# SCH.net
KiCad netlist of a schematic drawn in EasyEDA Pro
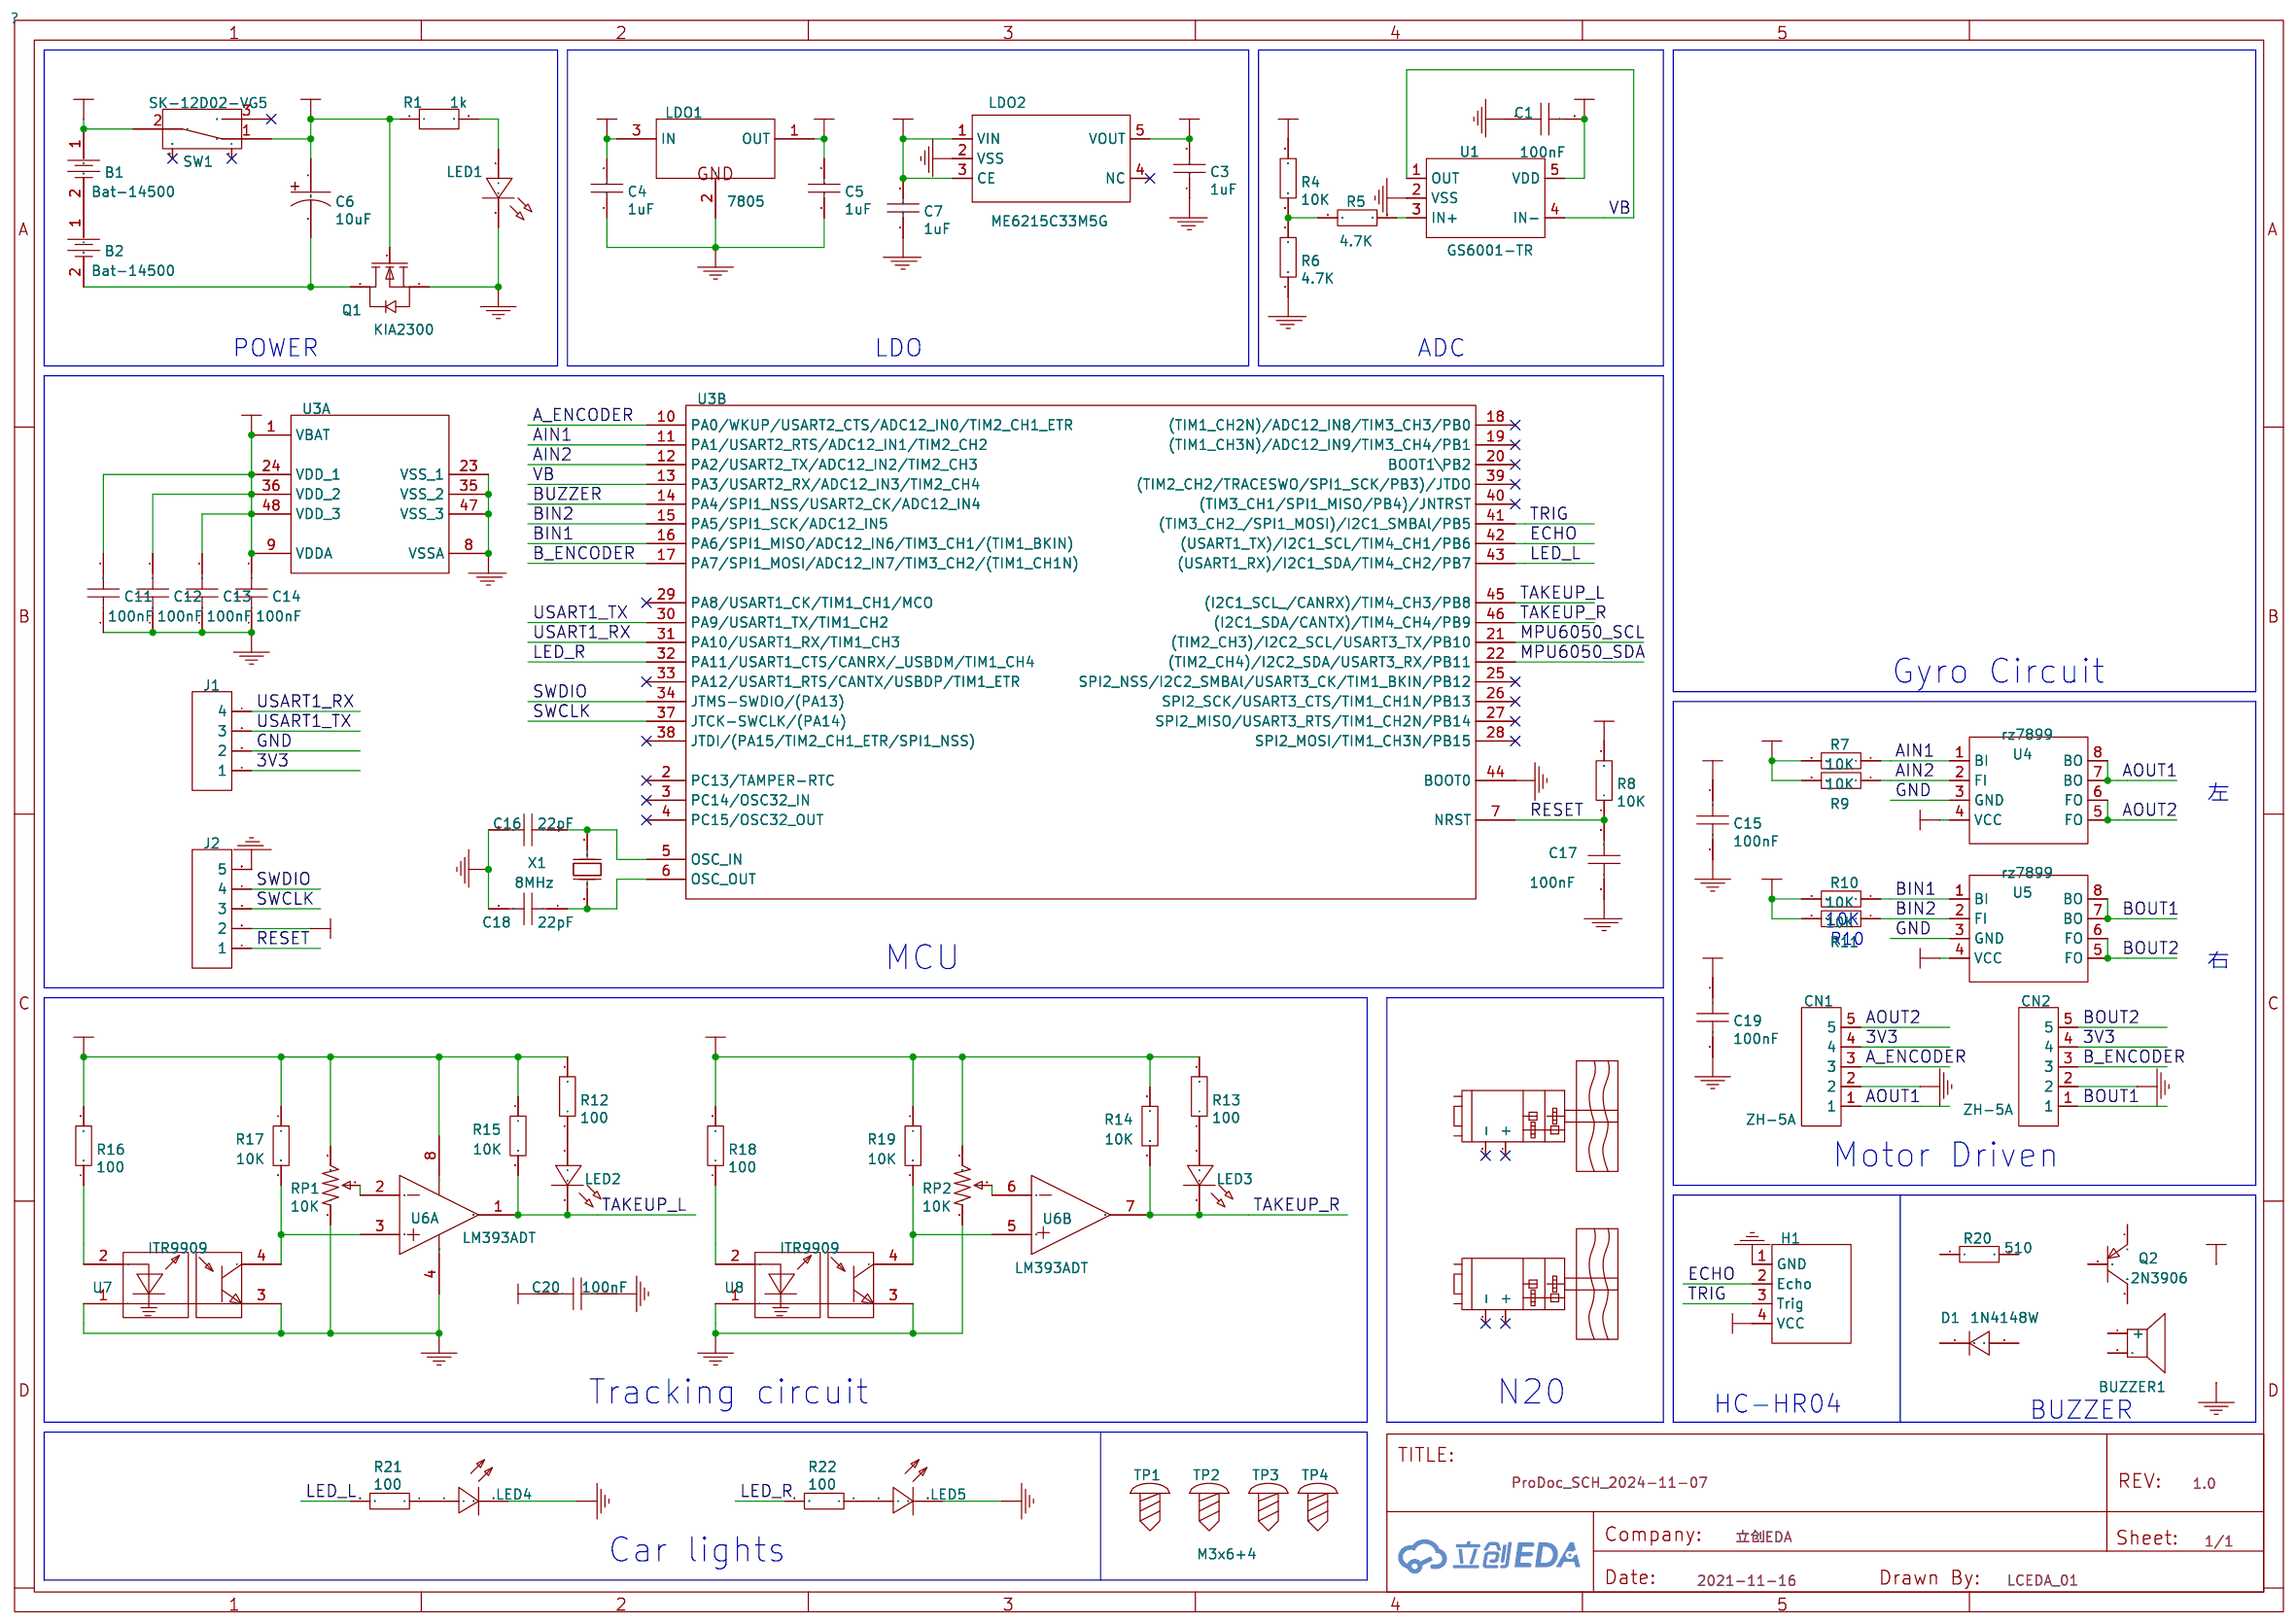
[diagram p0: schematic sheet]

(export (version "E")
  (design (tool "Eeschema 10.0.6"))
  (components
    (comp (ref "ASS_1")
      (value "直流电机N20")
      (footprint "easyedapro:直流电机N20_水平装配")
      (libsource (lib "easyedapro") (part "直流电机N20"))
    )
    (comp (ref "ASS_2")
      (value "直流电机N20")
      (footprint "easyedapro:直流电机N20_水平装配")
      (libsource (lib "easyedapro") (part "直流电机N20"))
    )
    (comp (ref "B1")
      (value "Bat-14500")
      (footprint "easyedapro:BAT-5AA_JX")
      (libsource (lib "easyedapro") (part "Bat-14500"))
    )
    (comp (ref "B2")
      (value "Bat-14500")
      (footprint "easyedapro:BAT-5AA_JX")
      (libsource (lib "easyedapro") (part "Bat-14500"))
    )
    (comp (ref "BUZZER1")
      (value "TMB12A12")
      (footprint "easyedapro:BUZ-TH_BD12.0-P7.60-D0.6-FD")
      (fields (field (name "Manufacturer") "HNDZ"))
      (libsource (lib "easyedapro") (part "TMB12A12"))
    )
    (comp (ref "C1")
      (value "100nF")
      (footprint "easyedapro:C0603")
      (fields (field (name "Manufacturer Part") "CC0603KRX7R9BB104") (field (name "Manufacturer") "YAGEO"))
      (libsource (lib "easyedapro") (part "100nF"))
    )
    (comp (ref "C3")
      (value "1uF")
      (footprint "easyedapro:C0603")
      (fields (field (name "Manufacturer Part") "CC0603KRX5R8BB105") (field (name "Manufacturer") "YAGEO"))
      (libsource (lib "easyedapro") (part "1uF"))
    )
    (comp (ref "C4")
      (value "1uF")
      (footprint "easyedapro:C0603")
      (fields (field (name "Manufacturer Part") "CC0603KRX5R8BB105") (field (name "Manufacturer") "YAGEO"))
      (libsource (lib "easyedapro") (part "1uF"))
    )
    (comp (ref "C5")
      (value "1uF")
      (footprint "easyedapro:C0603")
      (fields (field (name "Manufacturer Part") "CC0603KRX5R8BB105") (field (name "Manufacturer") "YAGEO"))
      (libsource (lib "easyedapro") (part "1uF"))
    )
    (comp (ref "C6")
      (value "10uF")
      (footprint "easyedapro:CAP-SMD_L3.2-W1.6")
      (fields (field (name "Manufacturer Part") "CA45-A-16V-10μF-K") (field (name "Manufacturer") "TORCH"))
      (libsource (lib "easyedapro") (part "10uF"))
    )
    (comp (ref "C7")
      (value "1uF")
      (footprint "easyedapro:C0603")
      (fields (field (name "Manufacturer Part") "CC0603KRX5R8BB105") (field (name "Manufacturer") "YAGEO"))
      (libsource (lib "easyedapro") (part "1uF"))
    )
    (comp (ref "C11")
      (value "100nF")
      (footprint "easyedapro:C0603")
      (fields (field (name "Manufacturer Part") "CC0603KRX7R9BB104") (field (name "Manufacturer") "YAGEO"))
      (libsource (lib "easyedapro") (part "100nF"))
    )
    (comp (ref "C12")
      (value "100nF")
      (footprint "easyedapro:C0603")
      (fields (field (name "Manufacturer Part") "CC0603KRX7R9BB104") (field (name "Manufacturer") "YAGEO"))
      (libsource (lib "easyedapro") (part "100nF"))
    )
    (comp (ref "C13")
      (value "100nF")
      (footprint "easyedapro:C0603")
      (fields (field (name "Manufacturer Part") "CC0603KRX7R9BB104") (field (name "Manufacturer") "YAGEO"))
      (libsource (lib "easyedapro") (part "100nF"))
    )
    (comp (ref "C14")
      (value "100nF")
      (footprint "easyedapro:C0603")
      (fields (field (name "Manufacturer Part") "CC0603KRX7R9BB104") (field (name "Manufacturer") "YAGEO"))
      (libsource (lib "easyedapro") (part "100nF"))
    )
    (comp (ref "C15")
      (value "100nF")
      (footprint "easyedapro:C0603")
      (fields (field (name "Manufacturer Part") "CC0603KRX7R9BB104") (field (name "Manufacturer") "YAGEO"))
      (libsource (lib "easyedapro") (part "100nF"))
    )
    (comp (ref "C16")
      (value "22pF")
      (footprint "easyedapro:C0603")
      (fields (field (name "Manufacturer Part") "CC0603FRNPO9BN220") (field (name "Manufacturer") "YAGEO"))
      (libsource (lib "easyedapro") (part "22pF"))
    )
    (comp (ref "C17")
      (value "100nF")
      (footprint "easyedapro:C0603")
      (fields (field (name "Manufacturer Part") "CC0603KRX7R9BB104") (field (name "Manufacturer") "YAGEO"))
      (libsource (lib "easyedapro") (part "100nF"))
    )
    (comp (ref "C18")
      (value "22pF")
      (footprint "easyedapro:C0603")
      (fields (field (name "Manufacturer Part") "CC0603FRNPO9BN220") (field (name "Manufacturer") "YAGEO"))
      (libsource (lib "easyedapro") (part "22pF"))
    )
    (comp (ref "C19")
      (value "100nF")
      (footprint "easyedapro:C0603")
      (fields (field (name "Manufacturer Part") "CC0603KRX7R9BB104") (field (name "Manufacturer") "YAGEO"))
      (libsource (lib "easyedapro") (part "100nF"))
    )
    (comp (ref "C20")
      (value "100nF")
      (footprint "easyedapro:C0603")
      (fields (field (name "Manufacturer Part") "CC0603KRX7R9BB104") (field (name "Manufacturer") "YAGEO"))
      (libsource (lib "easyedapro") (part "100nF"))
    )
    (comp (ref "CN1")
      (value "ZH-5A")
      (footprint "easyedapro:CONN-TH_5P-P1.50_ZH-5A")
      (fields (field (name "Manufacturer") "BOOMELE"))
      (libsource (lib "easyedapro") (part "ZH-5A"))
    )
    (comp (ref "CN2")
      (value "ZH-5A")
      (footprint "easyedapro:CONN-TH_5P-P1.50_ZH-5A")
      (fields (field (name "Manufacturer") "BOOMELE"))
      (libsource (lib "easyedapro") (part "ZH-5A"))
    )
    (comp (ref "D1")
      (value "1N4148W")
      (footprint "easyedapro:SOD-123FL_L2.6-W1.6-LS3.4-RD")
      (fields (field (name "Manufacturer") "Tak Cheong"))
      (libsource (lib "easyedapro") (part "1N4148W"))
    )
    (comp (ref "H1")
      (value "超声波测距模块_HC-HR04")
      (footprint "easyedapro:HC-HR04")
      (libsource (lib "easyedapro") (part "超声波测距模块_HC-HR04"))
    )
    (comp (ref "J1")
      (value "HDR-M-2.54_1x4")
      (footprint "easyedapro:HDR-M-2.54_1X4")
      (libsource (lib "easyedapro") (part "HDR-M-2.54_1x4"))
    )
    (comp (ref "J2")
      (value "HDR-M-2.54_1x5")
      (footprint "easyedapro:HDR-M-2.54_1X5")
      (libsource (lib "easyedapro") (part "HDR-M-2.54_1x5"))
    )
    (comp (ref "LDO1")
      (value "7805")
      (footprint "easyedapro:SOT-89-3_L4.5-W2.5-P1.50-LS4.2-BR")
      (fields (field (name "Manufacturer Part") "CJ78L05") (field (name "Manufacturer") "CJ"))
      (libsource (lib "easyedapro") (part "7805"))
    )
    (comp (ref "LDO2")
      (value "ME6215C33M5G")
      (footprint "easyedapro:SOT-23-5_L3.0-W1.7-P0.95-LS2.8-BR")
      (fields (field (name "Manufacturer") "MICRONE"))
      (libsource (lib "easyedapro") (part "ME6215C33M5G"))
    )
    (comp (ref "LED1")
      (value "LED-0603_R")
      (footprint "easyedapro:LED0603_RED")
      (fields
        (field (name "Manufacturer Part") "19-217/R6C-AL1M2VY/3T")
        (field (name "Manufacturer") "EVERLIGHT(台湾亿光)")
      )
      (libsource (lib "easyedapro") (part "LED-0603_R"))
    )
    (comp (ref "LED2")
      (value "LED-0805_G")
      (footprint "easyedapro:LED0603_GREEN")
      (fields (field (name "Manufacturer Part") "NCD0805G1") (field (name "Manufacturer") "国星光电"))
      (libsource (lib "easyedapro") (part "LED-0805_G"))
    )
    (comp (ref "LED3")
      (value "LED-0805_G")
      (footprint "easyedapro:LED0603_GREEN")
      (fields (field (name "Manufacturer Part") "NCD0805G1") (field (name "Manufacturer") "国星光电"))
      (libsource (lib "easyedapro") (part "LED-0805_G"))
    )
    (comp (ref "LED4")
      (value "TJ-L5FCMYGTDLSFLC6TW-A5")
      (footprint "easyedapro:LED-TH-5MM_P2.54-L")
      (fields (field (name "Manufacturer") "TOGIALED"))
      (libsource (lib "easyedapro") (part "TJ-L5FCMYGTDLSFLC6TW-A5"))
    )
    (comp (ref "LED5")
      (value "TJ-L5FCMYGTDLSFLC6TW-A5")
      (footprint "easyedapro:LED-TH-5MM_P2.54-L")
      (fields (field (name "Manufacturer") "TOGIALED"))
      (libsource (lib "easyedapro") (part "TJ-L5FCMYGTDLSFLC6TW-A5"))
    )
    (comp (ref "Q1")
      (value "KIA2300")
      (footprint "easyedapro:SOT-23_L2.9-W1.3-P1.90-LS2.4-BR")
      (fields (field (name "Manufacturer") "KIA"))
      (libsource (lib "easyedapro") (part "KIA2300"))
    )
    (comp (ref "Q2")
      (value "2N3906")
      (footprint "easyedapro:SOT-23-3_L2.9-W1.6-P1.90-LS2.8-TR-CW")
      (fields (field (name "Manufacturer Part") "2N3906S-RTK/PS") (field (name "Manufacturer") "KEC"))
      (libsource (lib "easyedapro") (part "2N3906"))
    )
    (comp (ref "R1") (value "1k") (footprint "easyedapro:R0603") (libsource (lib "easyedapro") (part "1k")))
    (comp (ref "R4")
      (value "10K")
      (footprint "easyedapro:R0603")
      (fields (field (name "Manufacturer Part") "AR03BTCX1002") (field (name "Manufacturer") "Viking Tech"))
      (libsource (lib "easyedapro") (part "10K"))
    )
    (comp (ref "R5")
      (value "4.7K")
      (footprint "easyedapro:R0603")
      (fields (field (name "Manufacturer Part") "RS-03K4701FT") (field (name "Manufacturer") "FH"))
      (libsource (lib "easyedapro") (part "4.7K"))
    )
    (comp (ref "R6")
      (value "4.7K")
      (footprint "easyedapro:R0603")
      (fields (field (name "Manufacturer Part") "RS-03K4701FT") (field (name "Manufacturer") "FH"))
      (libsource (lib "easyedapro") (part "4.7K"))
    )
    (comp (ref "R7")
      (value "10K")
      (footprint "easyedapro:R0603")
      (fields (field (name "Manufacturer Part") "AR03BTCX1002") (field (name "Manufacturer") "Viking Tech"))
      (libsource (lib "easyedapro") (part "10K"))
    )
    (comp (ref "R8")
      (value "10K")
      (footprint "easyedapro:R0603")
      (fields (field (name "Manufacturer Part") "AR03BTCX1002") (field (name "Manufacturer") "Viking Tech"))
      (libsource (lib "easyedapro") (part "10K"))
    )
    (comp (ref "R9")
      (value "10K")
      (footprint "easyedapro:R0603")
      (fields (field (name "Manufacturer Part") "AR03BTCX1002") (field (name "Manufacturer") "Viking Tech"))
      (libsource (lib "easyedapro") (part "10K"))
    )
    (comp (ref "R10")
      (value "10K")
      (footprint "easyedapro:R0603")
      (fields (field (name "Manufacturer Part") "AR03BTCX1002") (field (name "Manufacturer") "Viking Tech"))
      (libsource (lib "easyedapro") (part "10K"))
    )
    (comp (ref "R11")
      (value "10K")
      (footprint "easyedapro:R0603")
      (fields (field (name "Manufacturer Part") "AR03BTCX1002") (field (name "Manufacturer") "Viking Tech"))
      (libsource (lib "easyedapro") (part "10K"))
    )
    (comp (ref "R12")
      (value "100")
      (footprint "easyedapro:R0603")
      (fields (field (name "Manufacturer Part") "RS-03K101JT") (field (name "Manufacturer") "FH"))
      (libsource (lib "easyedapro") (part "100"))
    )
    (comp (ref "R13")
      (value "100")
      (footprint "easyedapro:R0603")
      (fields (field (name "Manufacturer Part") "RS-03K101JT") (field (name "Manufacturer") "FH"))
      (libsource (lib "easyedapro") (part "100"))
    )
    (comp (ref "R14")
      (value "10K")
      (footprint "easyedapro:R0603")
      (fields (field (name "Manufacturer Part") "AR03BTCX1002") (field (name "Manufacturer") "Viking Tech"))
      (libsource (lib "easyedapro") (part "10K"))
    )
    (comp (ref "R15")
      (value "10K")
      (footprint "easyedapro:R0603")
      (fields (field (name "Manufacturer Part") "AR03BTCX1002") (field (name "Manufacturer") "Viking Tech"))
      (libsource (lib "easyedapro") (part "10K"))
    )
    (comp (ref "R16")
      (value "100")
      (footprint "easyedapro:R0603")
      (fields (field (name "Manufacturer Part") "RS-03K101JT") (field (name "Manufacturer") "FH"))
      (libsource (lib "easyedapro") (part "100"))
    )
    (comp (ref "R17")
      (value "10K")
      (footprint "easyedapro:R0603")
      (fields (field (name "Manufacturer Part") "AR03BTCX1002") (field (name "Manufacturer") "Viking Tech"))
      (libsource (lib "easyedapro") (part "10K"))
    )
    (comp (ref "R18")
      (value "100")
      (footprint "easyedapro:R0603")
      (fields (field (name "Manufacturer Part") "RS-03K101JT") (field (name "Manufacturer") "FH"))
      (libsource (lib "easyedapro") (part "100"))
    )
    (comp (ref "R19")
      (value "10K")
      (footprint "easyedapro:R0603")
      (fields (field (name "Manufacturer Part") "AR03BTCX1002") (field (name "Manufacturer") "Viking Tech"))
      (libsource (lib "easyedapro") (part "10K"))
    )
    (comp (ref "R20")
      (value "510")
      (footprint "easyedapro:R0603")
      (fields (field (name "Manufacturer Part") "ERJUP3J511V") (field (name "Manufacturer") "PANASONIC"))
      (libsource (lib "easyedapro") (part "510"))
    )
    (comp (ref "R21")
      (value "100")
      (footprint "easyedapro:R0603")
      (fields (field (name "Manufacturer Part") "RS-03K101JT") (field (name "Manufacturer") "FH"))
      (libsource (lib "easyedapro") (part "100"))
    )
    (comp (ref "R22")
      (value "100")
      (footprint "easyedapro:R0603")
      (fields (field (name "Manufacturer Part") "RS-03K101JT") (field (name "Manufacturer") "FH"))
      (libsource (lib "easyedapro") (part "100"))
    )
    (comp (ref "RP1") (value "10K") (footprint "easyedapro:10K贴片可调电阻") (libsource (lib "") (part "10K_1")))
    (comp (ref "RP2") (value "10K") (footprint "easyedapro:10K贴片可调电阻") (libsource (lib "") (part "10K_1")))
    (comp (ref "SW1")
      (value "SK-12D02-VG5")
      (footprint "easyedapro:SW-TH_SK-12D02VG3")
      (fields (field (name "Manufacturer") "Rectangular Connectors - Contacts"))
      (libsource (lib "easyedapro") (part "SK-12D02-VG5"))
    )
    (comp (ref "TP1")
      (value "M3x6+4")
      (footprint "easyedapro:M3铜柱")
      (libsource (lib "easyedapro") (part "M3x6+4"))
    )
    (comp (ref "TP2")
      (value "M3x6+4")
      (footprint "easyedapro:M3铜柱")
      (libsource (lib "easyedapro") (part "M3x6+4"))
    )
    (comp (ref "TP3")
      (value "M3x6+4")
      (footprint "easyedapro:M3铜柱")
      (libsource (lib "easyedapro") (part "M3x6+4"))
    )
    (comp (ref "TP4")
      (value "M3x6+4")
      (footprint "easyedapro:M3铜柱")
      (libsource (lib "easyedapro") (part "M3x6+4"))
    )
    (comp (ref "U1")
      (value "GS6001-TR")
      (footprint "easyedapro:SOT-23-5_L3.0-W1.7-P0.95-LS2.8-BR")
      (fields (field (name "Manufacturer") "Gainsil"))
      (libsource (lib "easyedapro") (part "GS6001-TR"))
    )
    (comp (ref "U3")
      (value "STM32F103C8T6")
      (footprint "easyedapro:LQFP-48_L7.0-W7.0-P0.50-LS9.0-BL")
      (libsource (lib "easyedapro") (part "STM32F103C8T6"))
    )
    (comp (ref "U4")
      (value "rz7899")
      (footprint "easyedapro:SOP-8_L4.9-W3.9-P1.27-LS6.0-BL")
      (fields (field (name "Manufacturer") "RZ"))
      (libsource (lib "easyedapro") (part "rz7899"))
    )
    (comp (ref "U5")
      (value "rz7899")
      (footprint "easyedapro:SOP-8_L4.9-W3.9-P1.27-LS6.0-BL")
      (fields (field (name "Manufacturer") "RZ"))
      (libsource (lib "easyedapro") (part "rz7899"))
    )
    (comp (ref "U6")
      (value "LM393ADT")
      (footprint "easyedapro:SOIC-8_L4.9-W3.9-P1.27-LS6.0-BL")
      (fields (field (name "Manufacturer") "STMicroelectronics"))
      (libsource (lib "easyedapro") (part "LM393ADT"))
    )
    (comp (ref "U7")
      (value "ITR9909")
      (footprint "easyedapro:OPTO-TH_ITR9909")
      (fields (field (name "Manufacturer") "EVERLIGHT"))
      (libsource (lib "easyedapro") (part "ITR9909"))
    )
    (comp (ref "U8")
      (value "ITR9909")
      (footprint "easyedapro:OPTO-TH_ITR9909")
      (fields (field (name "Manufacturer") "EVERLIGHT"))
      (libsource (lib "easyedapro") (part "ITR9909"))
    )
    (comp (ref "X1")
      (value "8MHz")
      (footprint "easyedapro:OSC-SMD_L5.0-W3.2")
      (fields (field (name "Manufacturer Part") "X50328MSB2GI") (field (name "Manufacturer") "YXC"))
      (libsource (lib "easyedapro") (part "8MHz"))
    )
  )
  (nets
    (net (code "1") (name "+5V") (class "Default")
      (node (ref "C5") (pin "2") (pinfunction "2_2") (pintype "input"))
      (node (ref "C7") (pin "2") (pinfunction "2_2") (pintype "input"))
      (node (ref "H1") (pin "4") (pinfunction "VCC_4") (pintype "unspecified"))
      (node (ref "LDO1") (pin "1") (pinfunction "OUT_1") (pintype "unspecified"))
      (node (ref "LDO2") (pin "1") (pinfunction "VIN_1") (pintype "unspecified"))
      (node (ref "LDO2") (pin "3") (pinfunction "CE_3") (pintype "unspecified"))
    )
    (net (code "2") (name "/AIN1") (class "Default")
      (node (ref "R7") (pin "1") (pinfunction "1_1") (pintype "unspecified"))
      (node (ref "U3") (pin "11") (pinfunction "PA1/USART2_RTS/ADC12_IN1/TIM2_CH2_11") (pintype "bidirectional"))
      (node (ref "U4") (pin "1") (pinfunction "BI_1") (pintype "unspecified"))
    )
    (net (code "3") (name "/AIN2") (class "Default")
      (node (ref "R9") (pin "1") (pinfunction "1_1") (pintype "unspecified"))
      (node (ref "U3") (pin "12") (pinfunction "PA2/USART2_TX/ADC12_IN2/TIM2_CH3_12") (pintype "bidirectional"))
      (node (ref "U4") (pin "2") (pinfunction "FI_2") (pintype "unspecified"))
    )
    (net (code "4") (name "/AOUT1") (class "Default")
      (node (ref "CN1") (pin "1") (pinfunction "1_1") (pintype "unspecified"))
      (node (ref "U4") (pin "7") (pinfunction "BO_7") (pintype "unspecified"))
      (node (ref "U4") (pin "8") (pinfunction "BO_8") (pintype "unspecified"))
    )
    (net (code "5") (name "/AOUT2") (class "Default")
      (node (ref "CN1") (pin "5") (pinfunction "5_5") (pintype "unspecified"))
      (node (ref "U4") (pin "5") (pinfunction "FO_5") (pintype "unspecified"))
      (node (ref "U4") (pin "6") (pinfunction "FO_6") (pintype "unspecified"))
    )
    (net (code "6") (name "/A_ENCODER") (class "Default")
      (node (ref "CN1") (pin "3") (pinfunction "3_3") (pintype "unspecified"))
      (node (ref "U3") (pin "10") (pinfunction "PA0/WKUP/USART2_CTS/ADC12_IN0/TIM2_CH1_ETR_10") (pintype "bidirectional"))
    )
    (net (code "7") (name "/BIN1") (class "Default")
      (node (ref "R10") (pin "1") (pinfunction "1_1") (pintype "unspecified"))
      (node (ref "U3") (pin "16") (pinfunction "PA6/SPI1_MISO/ADC12_IN6/TIM3_CH1/(TIM1_BKIN)_16") (pintype "bidirectional"))
      (node (ref "U5") (pin "1") (pinfunction "BI_1") (pintype "unspecified"))
    )
    (net (code "8") (name "/BIN2") (class "Default")
      (node (ref "R11") (pin "1") (pinfunction "1_1") (pintype "unspecified"))
      (node (ref "U3") (pin "15") (pinfunction "PA5/SPI1_SCK/ADC12_IN5_15") (pintype "bidirectional"))
      (node (ref "U5") (pin "2") (pinfunction "FI_2") (pintype "unspecified"))
    )
    (net (code "9") (name "/BOUT1") (class "Default")
      (node (ref "CN2") (pin "1") (pinfunction "1_1") (pintype "unspecified"))
      (node (ref "U5") (pin "7") (pinfunction "BO_7") (pintype "unspecified"))
      (node (ref "U5") (pin "8") (pinfunction "BO_8") (pintype "unspecified"))
    )
    (net (code "10") (name "/BOUT2") (class "Default")
      (node (ref "CN2") (pin "5") (pinfunction "5_5") (pintype "unspecified"))
      (node (ref "U5") (pin "5") (pinfunction "FO_5") (pintype "unspecified"))
      (node (ref "U5") (pin "6") (pinfunction "FO_6") (pintype "unspecified"))
    )
    (net (code "11") (name "/BUZZER") (class "Default")
      (node (ref "U3") (pin "14") (pinfunction "PA4/SPI1_NSS/USART2_CK/ADC12_IN4_14") (pintype "bidirectional"))
    )
    (net (code "12") (name "/B_ENCODER") (class "Default")
      (node (ref "CN2") (pin "3") (pinfunction "3_3") (pintype "unspecified"))
      (node (ref "U3") (pin "17") (pinfunction "PA7/SPI1_MOSI/ADC12_IN7/TIM3_CH2/(TIM1_CH1N)_17") (pintype "bidirectional"))
    )
    (net (code "13") (name "/ECHO") (class "Default")
      (node (ref "H1") (pin "2") (pinfunction "Echo_2") (pintype "unspecified"))
      (node (ref "U3") (pin "42") (pinfunction "(USART1_TX)/I2C1_SCL/TIM4_CH1/PB6_42") (pintype "bidirectional"))
    )
    (net (code "14") (name "/LED_L") (class "Default")
      (node (ref "R21") (pin "2") (pinfunction "2_2") (pintype "input"))
      (node (ref "U3") (pin "43") (pinfunction "(USART1_RX)/I2C1_SDA/TIM4_CH2/PB7_43") (pintype "bidirectional"))
    )
    (net (code "15") (name "/LED_R") (class "Default")
      (node (ref "R22") (pin "2") (pinfunction "2_2") (pintype "input"))
      (node (ref "U3") (pin "32") (pinfunction "PA11/USART1_CTS/CANRX/_USBDM/TIM1_CH4_32") (pintype "bidirectional"))
    )
    (net (code "16") (name "/MPU6050_SCL") (class "Default")
      (node (ref "U3") (pin "21") (pinfunction "(TIM2_CH3)/I2C2_SCL/USART3_TX/PB10_21") (pintype "bidirectional"))
    )
    (net (code "17") (name "/MPU6050_SDA") (class "Default")
      (node (ref "U3") (pin "22") (pinfunction "(TIM2_CH4)/I2C2_SDA/USART3_RX/PB11_22") (pintype "bidirectional"))
    )
    (net (code "18") (name "/RESET") (class "Default")
      (node (ref "C17") (pin "2") (pinfunction "2_2") (pintype "unspecified"))
      (node (ref "J2") (pin "1") (pinfunction "1_1") (pintype "unspecified"))
      (node (ref "R8") (pin "1") (pinfunction "1_1") (pintype "unspecified"))
      (node (ref "U3") (pin "7") (pinfunction "NRST_7") (pintype "bidirectional"))
    )
    (net (code "19") (name "/SWCLK") (class "Default")
      (node (ref "J2") (pin "3") (pinfunction "3_3") (pintype "unspecified"))
      (node (ref "U3") (pin "37") (pinfunction "JTCK-SWCLK/(PA14)_37") (pintype "bidirectional"))
    )
    (net (code "20") (name "/SWDIO") (class "Default")
      (node (ref "J2") (pin "4") (pinfunction "4_4") (pintype "unspecified"))
      (node (ref "U3") (pin "34") (pinfunction "JTMS-SWDIO/(PA13)_34") (pintype "bidirectional"))
    )
    (net (code "21") (name "/TAKEUP_L") (class "Default")
      (node (ref "LED2") (pin "2") (pinfunction "2_2") (pintype "unspecified"))
      (node (ref "R15") (pin "2") (pinfunction "2_2") (pintype "unspecified"))
      (node (ref "U3") (pin "45") (pinfunction "(I2C1_SCL_/CANRX)/TIM4_CH3/PB8_45") (pintype "bidirectional"))
      (node (ref "U6") (pin "1") (pinfunction "OUT_1") (pintype "output"))
    )
    (net (code "22") (name "/TAKEUP_R") (class "Default")
      (node (ref "LED3") (pin "2") (pinfunction "2_2") (pintype "unspecified"))
      (node (ref "R14") (pin "2") (pinfunction "2_2") (pintype "unspecified"))
      (node (ref "U3") (pin "46") (pinfunction "(I2C1_SDA/CANTX)/TIM4_CH4/PB9_46") (pintype "bidirectional"))
      (node (ref "U6") (pin "7") (pinfunction "OUT_7") (pintype "output"))
    )
    (net (code "23") (name "/TRIG") (class "Default")
      (node (ref "H1") (pin "3") (pinfunction "Trig_3") (pintype "unspecified"))
      (node (ref "U3") (pin "41") (pinfunction "(TIM3_CH2_/SPI1_MOSI)/I2C1_SMBAl/PB5_41") (pintype "bidirectional"))
    )
    (net (code "24") (name "/USART1_RX") (class "Default")
      (node (ref "J1") (pin "4") (pinfunction "4_4") (pintype "unspecified"))
      (node (ref "U3") (pin "31") (pinfunction "PA10/USART1_RX/TIM1_CH3_31") (pintype "bidirectional"))
    )
    (net (code "25") (name "/USART1_TX") (class "Default")
      (node (ref "J1") (pin "3") (pinfunction "3_3") (pintype "unspecified"))
      (node (ref "U3") (pin "30") (pinfunction "PA9/USART1_TX/TIM1_CH2_30") (pintype "bidirectional"))
    )
    (net (code "26") (name "/VB") (class "Default")
      (node (ref "U1") (pin "1") (pinfunction "OUT_1") (pintype "unspecified"))
      (node (ref "U1") (pin "4") (pinfunction "IN-_4") (pintype "unspecified"))
      (node (ref "U3") (pin "13") (pinfunction "PA3/USART2_RX/ADC12_IN3/TIM2_CH4_13") (pintype "bidirectional"))
    )
    (net (code "27") (name "3V3") (class "Default")
      (node (ref "C1") (pin "2") (pinfunction "2_2") (pintype "unspecified"))
      (node (ref "C11") (pin "2") (pinfunction "2_2") (pintype "unspecified"))
      (node (ref "C12") (pin "2") (pinfunction "2_2") (pintype "unspecified"))
      (node (ref "C13") (pin "2") (pinfunction "2_2") (pintype "unspecified"))
      (node (ref "C14") (pin "2") (pinfunction "2_2") (pintype "unspecified"))
      (node (ref "C20") (pin "1") (pinfunction "1_1") (pintype "unspecified"))
      (node (ref "C3") (pin "2") (pinfunction "2_2") (pintype "input"))
      (node (ref "CN1") (pin "4") (pinfunction "4_4") (pintype "unspecified"))
      (node (ref "CN2") (pin "4") (pinfunction "4_4") (pintype "unspecified"))
      (node (ref "J1") (pin "1") (pinfunction "1_1") (pintype "unspecified"))
      (node (ref "J2") (pin "2") (pinfunction "2_2") (pintype "unspecified"))
      (node (ref "LDO2") (pin "5") (pinfunction "VOUT_5") (pintype "unspecified"))
      (node (ref "R10") (pin "2") (pinfunction "2_2") (pintype "unspecified"))
      (node (ref "R11") (pin "2") (pinfunction "2_2") (pintype "unspecified"))
      (node (ref "R12") (pin "2") (pinfunction "2_2") (pintype "input"))
      (node (ref "R13") (pin "2") (pinfunction "2_2") (pintype "input"))
      (node (ref "R14") (pin "1") (pinfunction "1_1") (pintype "unspecified"))
      (node (ref "R15") (pin "1") (pinfunction "1_1") (pintype "unspecified"))
      (node (ref "R16") (pin "2") (pinfunction "2_2") (pintype "input"))
      (node (ref "R17") (pin "1") (pinfunction "1_1") (pintype "unspecified"))
      (node (ref "R18") (pin "2") (pinfunction "2_2") (pintype "input"))
      (node (ref "R19") (pin "1") (pinfunction "1_1") (pintype "unspecified"))
      (node (ref "R7") (pin "2") (pinfunction "2_2") (pintype "unspecified"))
      (node (ref "R8") (pin "2") (pinfunction "2_2") (pintype "unspecified"))
      (node (ref "R9") (pin "2") (pinfunction "2_2") (pintype "unspecified"))
      (node (ref "RP1") (pin "3") (pinfunction "3_3") (pintype "unspecified"))
      (node (ref "RP2") (pin "3") (pinfunction "3_3") (pintype "unspecified"))
      (node (ref "U1") (pin "5") (pinfunction "VDD_5") (pintype "unspecified"))
      (node (ref "U3") (pin "1") (pinfunction "VBAT_1") (pintype "unspecified"))
      (node (ref "U3") (pin "24") (pinfunction "VDD_1_24") (pintype "unspecified"))
      (node (ref "U3") (pin "36") (pinfunction "VDD_2_36") (pintype "unspecified"))
      (node (ref "U3") (pin "48") (pinfunction "VDD_3_48") (pintype "unspecified"))
      (node (ref "U3") (pin "9") (pinfunction "VDDA_9") (pintype "unspecified"))
      (node (ref "U6") (pin "8") (pinfunction "V+_8") (pintype "unspecified"))
    )
    (net (code "28") (name "GND") (class "Default")
      (node (ref "C1") (pin "1") (pinfunction "1_1") (pintype "unspecified"))
      (node (ref "C11") (pin "1") (pinfunction "1_1") (pintype "unspecified"))
      (node (ref "C12") (pin "1") (pinfunction "1_1") (pintype "unspecified"))
      (node (ref "C13") (pin "1") (pinfunction "1_1") (pintype "unspecified"))
      (node (ref "C14") (pin "1") (pinfunction "1_1") (pintype "unspecified"))
      (node (ref "C15") (pin "2") (pinfunction "2_2") (pintype "unspecified"))
      (node (ref "C16") (pin "2") (pinfunction "2_2") (pintype "unspecified"))
      (node (ref "C17") (pin "1") (pinfunction "1_1") (pintype "unspecified"))
      (node (ref "C18") (pin "2") (pinfunction "2_2") (pintype "unspecified"))
      (node (ref "C19") (pin "2") (pinfunction "2_2") (pintype "unspecified"))
      (node (ref "C20") (pin "2") (pinfunction "2_2") (pintype "unspecified"))
      (node (ref "C3") (pin "1") (pinfunction "1_1") (pintype "input"))
      (node (ref "C4") (pin "1") (pinfunction "1_1") (pintype "input"))
      (node (ref "C5") (pin "1") (pinfunction "1_1") (pintype "input"))
      (node (ref "C7") (pin "1") (pinfunction "1_1") (pintype "input"))
      (node (ref "CN1") (pin "2") (pinfunction "2_2") (pintype "unspecified"))
      (node (ref "CN2") (pin "2") (pinfunction "2_2") (pintype "unspecified"))
      (node (ref "H1") (pin "1") (pinfunction "GND_1") (pintype "unspecified"))
      (node (ref "J1") (pin "2") (pinfunction "2_2") (pintype "unspecified"))
      (node (ref "J2") (pin "5") (pinfunction "5_5") (pintype "unspecified"))
      (node (ref "LDO1") (pin "2") (pinfunction "GND_2") (pintype "unspecified"))
      (node (ref "LDO2") (pin "2") (pinfunction "VSS_2") (pintype "unspecified"))
      (node (ref "LED1") (pin "2") (pinfunction "2_2") (pintype "unspecified"))
      (node (ref "LED4") (pin "2") (pinfunction "2_2") (pintype "unspecified"))
      (node (ref "LED5") (pin "2") (pinfunction "2_2") (pintype "unspecified"))
      (node (ref "Q1") (pin "2") (pinfunction "S_2") (pintype "unspecified"))
      (node (ref "R6") (pin "1") (pinfunction "1_1") (pintype "unspecified"))
      (node (ref "RP1") (pin "1") (pinfunction "1_1") (pintype "unspecified"))
      (node (ref "RP2") (pin "1") (pinfunction "1_1") (pintype "unspecified"))
      (node (ref "U1") (pin "2") (pinfunction "VSS_2") (pintype "unspecified"))
      (node (ref "U3") (pin "23") (pinfunction "VSS_1_23") (pintype "unspecified"))
      (node (ref "U3") (pin "35") (pinfunction "VSS_2_35") (pintype "unspecified"))
      (node (ref "U3") (pin "44") (pinfunction "BOOT0_44") (pintype "unspecified"))
      (node (ref "U3") (pin "47") (pinfunction "VSS_3_47") (pintype "unspecified"))
      (node (ref "U3") (pin "8") (pinfunction "VSSA_8") (pintype "unspecified"))
      (node (ref "U4") (pin "3") (pinfunction "GND_3") (pintype "unspecified"))
      (node (ref "U5") (pin "3") (pinfunction "GND_3") (pintype "unspecified"))
      (node (ref "U6") (pin "4") (pinfunction "GND_4") (pintype "unspecified"))
      (node (ref "U7") (pin "1") (pinfunction "1_1") (pintype "unspecified"))
      (node (ref "U7") (pin "3") (pinfunction "3_3") (pintype "unspecified"))
      (node (ref "U8") (pin "1") (pinfunction "1_1") (pintype "unspecified"))
      (node (ref "U8") (pin "3") (pinfunction "3_3") (pintype "unspecified"))
    )
    (net (code "29") (name "Net-(B1-Pad2)") (class "Default")
      (node (ref "B1") (pin "2") (pinfunction "2_2") (pintype "unspecified"))
      (node (ref "B2") (pin "1") (pinfunction "1_1") (pintype "unspecified"))
    )
    (net (code "30") (name "Net-(LED1-Pad1)") (class "Default")
      (node (ref "LED1") (pin "1") (pinfunction "1_1") (pintype "unspecified"))
      (node (ref "R1") (pin "2") (pinfunction "2_2") (pintype "unspecified"))
    )
    (net (code "31") (name "Net-(LED2-Pad1)") (class "Default")
      (node (ref "LED2") (pin "1") (pinfunction "1_1") (pintype "unspecified"))
      (node (ref "R12") (pin "1") (pinfunction "1_1") (pintype "input"))
    )
    (net (code "32") (name "Net-(LED3-Pad1)") (class "Default")
      (node (ref "LED3") (pin "1") (pinfunction "1_1") (pintype "unspecified"))
      (node (ref "R13") (pin "1") (pinfunction "1_1") (pintype "input"))
    )
    (net (code "33") (name "Net-(LED4-Pad1)") (class "Default")
      (node (ref "LED4") (pin "1") (pinfunction "1_1") (pintype "unspecified"))
      (node (ref "R21") (pin "1") (pinfunction "1_1") (pintype "input"))
    )
    (net (code "34") (name "Net-(LED5-Pad1)") (class "Default")
      (node (ref "LED5") (pin "1") (pinfunction "1_1") (pintype "unspecified"))
      (node (ref "R22") (pin "1") (pinfunction "1_1") (pintype "input"))
    )
    (net (code "35") (name "Net-(Q1-D)") (class "Default")
      (node (ref "B2") (pin "2") (pinfunction "2_2") (pintype "unspecified"))
      (node (ref "C6") (pin "2") (pinfunction "2_2") (pintype "unspecified"))
      (node (ref "Q1") (pin "3") (pinfunction "D_3") (pintype "unspecified"))
    )
    (net (code "36") (name "Net-(R4-Pad2)") (class "Default")
      (node (ref "R4") (pin "2") (pinfunction "2_2") (pintype "unspecified"))
      (node (ref "R5") (pin "1") (pinfunction "1_1") (pintype "unspecified"))
      (node (ref "R6") (pin "2") (pinfunction "2_2") (pintype "unspecified"))
    )
    (net (code "37") (name "Net-(R16-Pad1)") (class "Default")
      (node (ref "R16") (pin "1") (pinfunction "1_1") (pintype "input"))
      (node (ref "U7") (pin "2") (pinfunction "2_2") (pintype "unspecified"))
    )
    (net (code "38") (name "Net-(R18-Pad1)") (class "Default")
      (node (ref "R18") (pin "1") (pinfunction "1_1") (pintype "input"))
      (node (ref "U8") (pin "2") (pinfunction "2_2") (pintype "unspecified"))
    )
    (net (code "39") (name "Net-(U1-IN+)") (class "Default")
      (node (ref "R5") (pin "2") (pinfunction "2_2") (pintype "unspecified"))
      (node (ref "U1") (pin "3") (pinfunction "IN+_3") (pintype "unspecified"))
    )
    (net (code "40") (name "Net-(U3B-OSC_IN)") (class "Default")
      (node (ref "C16") (pin "1") (pinfunction "1_1") (pintype "unspecified"))
      (node (ref "U3") (pin "5") (pinfunction "OSC_IN_5") (pintype "bidirectional"))
      (node (ref "X1") (pin "2") (pinfunction "OSC2_2") (pintype "input"))
    )
    (net (code "41") (name "Net-(U3B-OSC_OUT)") (class "Default")
      (node (ref "C18") (pin "1") (pinfunction "1_1") (pintype "unspecified"))
      (node (ref "U3") (pin "6") (pinfunction "OSC_OUT_6") (pintype "bidirectional"))
      (node (ref "X1") (pin "1") (pinfunction "OSC1_1") (pintype "input"))
    )
    (net (code "42") (name "Net-(U6A-IN+)") (class "Default")
      (node (ref "R17") (pin "2") (pinfunction "2_2") (pintype "unspecified"))
      (node (ref "U6") (pin "3") (pinfunction "IN+_3") (pintype "unspecified"))
      (node (ref "U7") (pin "4") (pinfunction "4_4") (pintype "unspecified"))
    )
    (net (code "43") (name "Net-(U6A-IN-)") (class "Default")
      (node (ref "RP1") (pin "2") (pinfunction "2_2") (pintype "unspecified"))
      (node (ref "U6") (pin "2") (pinfunction "IN-_2") (pintype "unspecified"))
    )
    (net (code "44") (name "Net-(U6B-IN+)") (class "Default")
      (node (ref "R19") (pin "2") (pinfunction "2_2") (pintype "unspecified"))
      (node (ref "U6") (pin "5") (pinfunction "IN+_5") (pintype "unspecified"))
      (node (ref "U8") (pin "4") (pinfunction "4_4") (pintype "unspecified"))
    )
    (net (code "45") (name "Net-(U6B-IN-)") (class "Default")
      (node (ref "RP2") (pin "2") (pinfunction "2_2") (pintype "unspecified"))
      (node (ref "U6") (pin "6") (pinfunction "IN-_6") (pintype "unspecified"))
    )
    (net (code "46") (name "VCC") (class "Default")
      (node (ref "C15") (pin "1") (pinfunction "1_1") (pintype "unspecified"))
      (node (ref "C19") (pin "1") (pinfunction "1_1") (pintype "unspecified"))
      (node (ref "C4") (pin "2") (pinfunction "2_2") (pintype "input"))
      (node (ref "C6") (pin "1") (pinfunction "1_1") (pintype "unspecified"))
      (node (ref "LDO1") (pin "3") (pinfunction "IN_3") (pintype "unspecified"))
      (node (ref "Q1") (pin "1") (pinfunction "G_1") (pintype "unspecified"))
      (node (ref "R1") (pin "1") (pinfunction "1_1") (pintype "unspecified"))
      (node (ref "R4") (pin "1") (pinfunction "1_1") (pintype "unspecified"))
      (node (ref "SW1") (pin "1") (pinfunction "1_1") (pintype "unspecified"))
      (node (ref "U4") (pin "4") (pinfunction "VCC_4") (pintype "unspecified"))
      (node (ref "U5") (pin "4") (pinfunction "VCC_4") (pintype "unspecified"))
    )
    (net (code "47") (name "VCC_IN") (class "Default")
      (node (ref "B1") (pin "1") (pinfunction "1_1") (pintype "unspecified"))
      (node (ref "SW1") (pin "2") (pinfunction "2_2") (pintype "unspecified"))
    )
    (net (code "48") (name "unconnected-(ASS_1-+-Pad1)") (class "Default")
      (node (ref "ASS_1") (pin "1") (pinfunction "+_1") (pintype "unspecified+no_connect"))
    )
    (net (code "49") (name "unconnected-(ASS_1---Pad2)") (class "Default")
      (node (ref "ASS_1") (pin "2") (pinfunction "-_2") (pintype "unspecified+no_connect"))
    )
    (net (code "50") (name "unconnected-(ASS_2-+-Pad1)") (class "Default")
      (node (ref "ASS_2") (pin "1") (pinfunction "+_1") (pintype "unspecified+no_connect"))
    )
    (net (code "51") (name "unconnected-(ASS_2---Pad2)") (class "Default")
      (node (ref "ASS_2") (pin "2") (pinfunction "-_2") (pintype "unspecified+no_connect"))
    )
    (net (code "52") (name "unconnected-(BUZZER1-+-Pad1)") (class "Default")
      (node (ref "BUZZER1") (pin "1") (pinfunction "+_1") (pintype "unspecified"))
    )
    (net (code "53") (name "unconnected-(BUZZER1-Pad2)") (class "Default")
      (node (ref "BUZZER1") (pin "2") (pinfunction "2_2") (pintype "unspecified"))
    )
    (net (code "54") (name "unconnected-(D1-Pad1)") (class "Default")
      (node (ref "D1") (pin "1") (pinfunction "1_1") (pintype "unspecified"))
    )
    (net (code "55") (name "unconnected-(D1-Pad2)") (class "Default")
      (node (ref "D1") (pin "2") (pinfunction "2_2") (pintype "unspecified"))
    )
    (net (code "56") (name "unconnected-(LDO2-NC-Pad4)") (class "Default")
      (node (ref "LDO2") (pin "4") (pinfunction "NC_4") (pintype "unspecified+no_connect"))
    )
    (net (code "57") (name "unconnected-(Q2-B-Pad2)") (class "Default")
      (node (ref "Q2") (pin "2") (pinfunction "B_2") (pintype "input"))
    )
    (net (code "58") (name "unconnected-(Q2-C-Pad3)") (class "Default")
      (node (ref "Q2") (pin "3") (pinfunction "C_3") (pintype "input"))
    )
    (net (code "59") (name "unconnected-(Q2-E-Pad1)") (class "Default")
      (node (ref "Q2") (pin "1") (pinfunction "E_1") (pintype "input"))
    )
    (net (code "60") (name "unconnected-(R20-Pad1)") (class "Default")
      (node (ref "R20") (pin "1") (pinfunction "1_1") (pintype "unspecified"))
    )
    (net (code "61") (name "unconnected-(R20-Pad2)") (class "Default")
      (node (ref "R20") (pin "2") (pinfunction "2_2") (pintype "unspecified"))
    )
    (net (code "62") (name "unconnected-(SW1-Pad3)") (class "Default")
      (node (ref "SW1") (pin "3") (pinfunction "3_3") (pintype "unspecified+no_connect"))
    )
    (net (code "63") (name "unconnected-(SW1-Pad4)") (class "Default")
      (node (ref "SW1") (pin "4") (pinfunction "4_4") (pintype "unspecified+no_connect"))
    )
    (net (code "64") (name "unconnected-(SW1-Pad5)") (class "Default")
      (node (ref "SW1") (pin "5") (pinfunction "5_5") (pintype "unspecified+no_connect"))
    )
    (net (code "65") (name "unconnected-(U3B-(TIM1_CH2N){slash}ADC12_IN8{slash}TIM3_CH3{slash}PB0-Pad18)") (class "Default")
      (node (ref "U3") (pin "18") (pinfunction "(TIM1_CH2N)/ADC12_IN8/TIM3_CH3/PB0_18") (pintype "bidirectional+no_connect"))
    )
    (net (code "66") (name "unconnected-(U3B-(TIM1_CH3N){slash}ADC12_IN9{slash}TIM3_CH4{slash}PB1-Pad19)") (class "Default")
      (node (ref "U3") (pin "19") (pinfunction "(TIM1_CH3N)/ADC12_IN9/TIM3_CH4/PB1_19") (pintype "bidirectional+no_connect"))
    )
    (net (code "67") (name "unconnected-(U3B-(TIM2_CH2{slash}TRACESWO{slash}SPI1_SCK{slash}PB3){slash}JTDO-Pad39)") (class "Default")
      (node (ref "U3") (pin "39") (pinfunction "(TIM2_CH2/TRACESWO/SPI1_SCK/PB3)/JTDO_39") (pintype "bidirectional+no_connect"))
    )
    (net (code "68") (name "unconnected-(U3B-(TIM3_CH1{slash}SPI1_MISO{slash}PB4){slash}JNTRST-Pad40)") (class "Default")
      (node (ref "U3") (pin "40") (pinfunction "(TIM3_CH1/SPI1_MISO/PB4)/JNTRST_40") (pintype "bidirectional+no_connect"))
    )
    (net (code "69") (name "unconnected-(U3B-BOOT1\\PB2-Pad20)") (class "Default")
      (node (ref "U3") (pin "20") (pinfunction "BOOT1\\PB2_20") (pintype "bidirectional+no_connect"))
    )
    (net (code "70") (name "unconnected-(U3B-JTDI{slash}(PA15{slash}TIM2_CH1_ETR{slash}SPI1_NSS)-Pad38)") (class "Default")
      (node (ref "U3") (pin "38") (pinfunction "JTDI/(PA15/TIM2_CH1_ETR/SPI1_NSS)_38") (pintype "bidirectional+no_connect"))
    )
    (net (code "71") (name "unconnected-(U3B-PA8{slash}USART1_CK{slash}TIM1_CH1{slash}MCO-Pad29)") (class "Default")
      (node (ref "U3") (pin "29") (pinfunction "PA8/USART1_CK/TIM1_CH1/MCO_29") (pintype "bidirectional+no_connect"))
    )
    (net (code "72") (name "unconnected-(U3B-PA12{slash}USART1_RTS{slash}CANTX{slash}USBDP{slash}TIM1_ETR-Pad33)") (class "Default")
      (node (ref "U3") (pin "33") (pinfunction "PA12/USART1_RTS/CANTX/USBDP/TIM1_ETR_33") (pintype "bidirectional+no_connect"))
    )
    (net (code "73") (name "unconnected-(U3B-PC13{slash}TAMPER-RTC-Pad2)") (class "Default")
      (node (ref "U3") (pin "2") (pinfunction "PC13/TAMPER-RTC_2") (pintype "bidirectional+no_connect"))
    )
    (net (code "74") (name "unconnected-(U3B-PC14{slash}OSC32_IN-Pad3)") (class "Default")
      (node (ref "U3") (pin "3") (pinfunction "PC14/OSC32_IN_3") (pintype "bidirectional+no_connect"))
    )
    (net (code "75") (name "unconnected-(U3B-PC15{slash}OSC32_OUT-Pad4)") (class "Default")
      (node (ref "U3") (pin "4") (pinfunction "PC15/OSC32_OUT_4") (pintype "bidirectional+no_connect"))
    )
    (net (code "76") (name "unconnected-(U3B-SPI2_MISO{slash}USART3_RTS{slash}TIM1_CH2N{slash}PB14-Pad27)") (class "Default")
      (node (ref "U3") (pin "27") (pinfunction "SPI2_MISO/USART3_RTS/TIM1_CH2N/PB14_27") (pintype "bidirectional+no_connect"))
    )
    (net (code "77") (name "unconnected-(U3B-SPI2_MOSI{slash}TIM1_CH3N{slash}PB15-Pad28)") (class "Default")
      (node (ref "U3") (pin "28") (pinfunction "SPI2_MOSI/TIM1_CH3N/PB15_28") (pintype "bidirectional+no_connect"))
    )
    (net (code "78") (name "unconnected-(U3B-SPI2_NSS{slash}I2C2_SMBAl{slash}USART3_CK{slash}TIM1_BKIN{slash}PB12-Pad25)") (class "Default")
      (node (ref "U3") (pin "25") (pinfunction "SPI2_NSS/I2C2_SMBAl/USART3_CK/TIM1_BKIN/PB12_25") (pintype "bidirectional+no_connect"))
    )
    (net (code "79") (name "unconnected-(U3B-SPI2_SCK{slash}USART3_CTS{slash}TIM1_CH1N{slash}PB13-Pad26)") (class "Default")
      (node (ref "U3") (pin "26") (pinfunction "SPI2_SCK/USART3_CTS/TIM1_CH1N/PB13_26") (pintype "bidirectional+no_connect"))
    )
  )
)
